# HCRT_STM32_Sch.net
KiCad netlist of a schematic drawn in Altium Designer
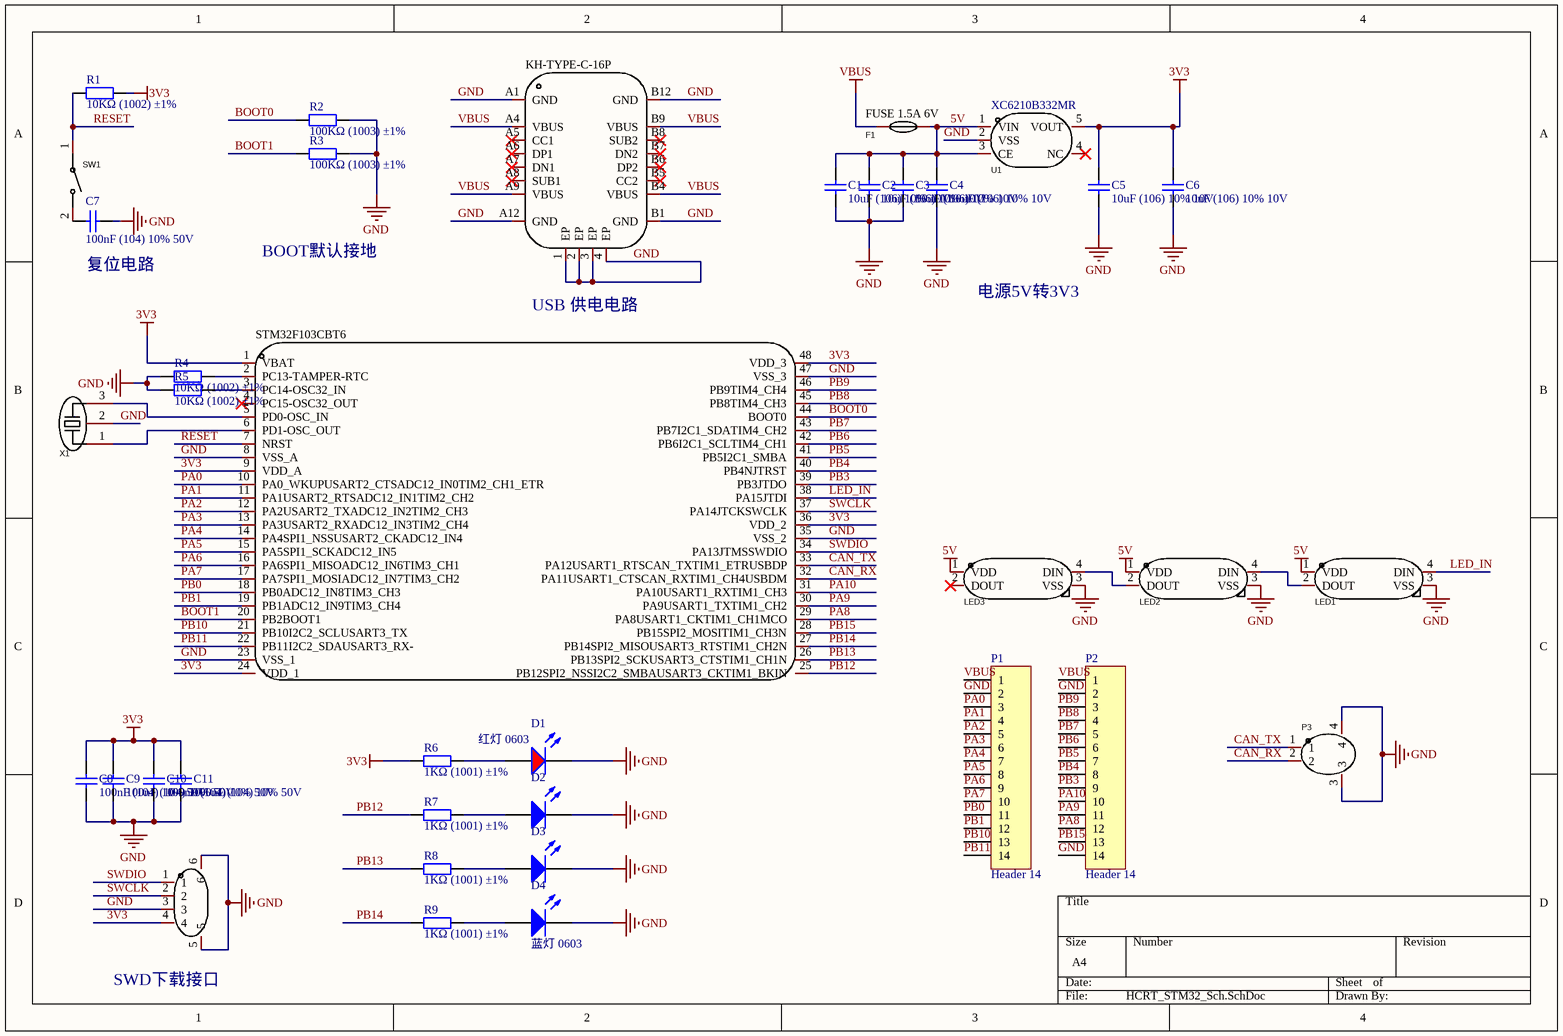
[diagram p0: HCRT_STM32_Sch.SchDoc]

(export (version "E")
  (design (tool "Eeschema 10.0.6"))
  (components
    (comp (ref "C1")
      (value "10uF (106) 10% 10V")
      (footprint "0603_C")
      (description "贴片电容")
      (libsource (lib "Miscellaneous Devices LC") (part "0603 10uF (106) 10% 10V"))
    )
    (comp (ref "C2")
      (value "10uF (106) 10% 10V")
      (footprint "0603_C")
      (description "贴片电容")
      (libsource (lib "Miscellaneous Devices LC") (part "0603 10uF (106) 10% 10V"))
    )
    (comp (ref "C3")
      (value "10uF (106) 10% 10V")
      (footprint "0603_C")
      (description "贴片电容")
      (libsource (lib "Miscellaneous Devices LC") (part "0603 10uF (106) 10% 10V"))
    )
    (comp (ref "C4")
      (value "10uF (106) 10% 10V")
      (footprint "0603_C")
      (description "贴片电容")
      (libsource (lib "Miscellaneous Devices LC") (part "0603 10uF (106) 10% 10V"))
    )
    (comp (ref "C5")
      (value "10uF (106) 10% 10V")
      (footprint "0603_C")
      (description "贴片电容")
      (libsource (lib "Miscellaneous Devices LC") (part "0603 10uF (106) 10% 10V"))
    )
    (comp (ref "C6")
      (value "10uF (106) 10% 10V")
      (footprint "0603_C")
      (description "贴片电容")
      (libsource (lib "Miscellaneous Devices LC") (part "0603 10uF (106) 10% 10V"))
    )
    (comp (ref "C7")
      (value "100nF (104) 10% 50V")
      (footprint "0603_C")
      (description "贴片电容")
      (libsource (lib "Miscellaneous Devices LC") (part "0603 100nF (104) 10% 50V"))
    )
    (comp (ref "C8")
      (value "100nF (104) 10% 50V")
      (footprint "0603_C")
      (description "贴片电容")
      (libsource (lib "Miscellaneous Devices LC") (part "0603 100nF (104) 10% 50V"))
    )
    (comp (ref "C9")
      (value "100nF (104) 10% 50V")
      (footprint "0603_C")
      (description "贴片电容")
      (libsource (lib "Miscellaneous Devices LC") (part "0603 100nF (104) 10% 50V"))
    )
    (comp (ref "C10")
      (value "100nF (104) 10% 50V")
      (footprint "0603_C")
      (description "贴片电容")
      (libsource (lib "Miscellaneous Devices LC") (part "0603 100nF (104) 10% 50V"))
    )
    (comp (ref "C11")
      (value "100nF (104) 10% 50V")
      (footprint "0603_C")
      (description "贴片电容")
      (libsource (lib "Miscellaneous Devices LC") (part "0603 100nF (104) 10% 50V"))
    )
    (comp (ref "CN1")
      (value "HC-1.25-4PWT")
      (footprint "CONN-SMD_4P-P1.25-HC-1.25-4PWT")
      (fields (field (name "MANUFACTURER") "HCTL(华灿天禄)"))
      (libsource (lib "zxy's_LIB") (part "HC-1.25-4PWT"))
    )
    (comp (ref "D1")
      (value "红灯 0603")
      (footprint "0603_LED_S1")
      (description "发光二极管")
      (libsource (lib "Miscellaneous Devices LC") (part "0603 红灯"))
    )
    (comp (ref "D2")
      (value "蓝灯 0603")
      (footprint "0603_LED_S1")
      (description "发光二极管")
      (libsource (lib "Miscellaneous Devices LC") (part "0603 蓝灯"))
    )
    (comp (ref "D3")
      (value "蓝灯 0603")
      (footprint "0603_LED_S1")
      (description "发光二极管")
      (libsource (lib "Miscellaneous Devices LC") (part "0603 蓝灯"))
    )
    (comp (ref "D4")
      (value "蓝灯 0603")
      (footprint "0603_LED_S1")
      (description "发光二极管")
      (libsource (lib "Miscellaneous Devices LC") (part "0603 蓝灯"))
    )
    (comp (ref "F1")
      (value "FUSE0603")
      (footprint "F0603")
      (fields (field (name "MANUFACTURER") "BHFUSE(佰宏)") (field (name "MANUFACTURER PART") "BSMD0603L-150"))
      (libsource (lib "zxy's_LIB") (part "FUSE0603"))
    )
    (comp (ref "LED1")
      (value "WS2812C")
      (footprint "LED-SMD_4P-L5.0-W5.0-LS5.4-TL-1")
      (fields (field (name "MANUFACTURER") "worldsemi"))
      (libsource (lib "zxy's_LIB") (part "WS2812C"))
    )
    (comp (ref "LED2")
      (value "WS2812C")
      (footprint "LED-SMD_4P-L5.0-W5.0-LS5.4-TL-1")
      (fields (field (name "MANUFACTURER") "worldsemi"))
      (libsource (lib "zxy's_LIB") (part "WS2812C"))
    )
    (comp (ref "LED3")
      (value "WS2812C")
      (footprint "LED-SMD_4P-L5.0-W5.0-LS5.4-TL-1")
      (fields (field (name "MANUFACTURER") "worldsemi"))
      (libsource (lib "zxy's_LIB") (part "WS2812C"))
    )
    (comp (ref "P1")
      (value "Header 14")
      (footprint "HDR1X14")
      (description "Header, 14-Pin")
      (fields (field (name "PUBLISHER") "Altium Limited"))
      (libsource (lib "Miscellaneous Connectors") (part "Header 14"))
    )
    (comp (ref "P2")
      (value "Header 14")
      (footprint "HDR1X14")
      (description "Header, 14-Pin")
      (fields (field (name "PUBLISHER") "Altium Limited"))
      (libsource (lib "Miscellaneous Connectors") (part "Header 14"))
    )
    (comp (ref "P3")
      (value "1.25_2P")
      (footprint "CONN-SMD_SM02B-GHS-TB-LF-SN")
      (fields (field (name "MANUFACTURER") "JST") (field (name "MANUFACTURER PART") "SM02B-GHS-TB(LF)(SN)"))
      (libsource (lib "zxy's_LIB") (part "1.25_2P"))
    )
    (comp (ref "R1")
      (value "10KΩ (1002) ±1%")
      (footprint "0603_R")
      (description "贴片电阻")
      (libsource (lib "Miscellaneous Devices LC") (part "0603 10KΩ (1002) 1%"))
    )
    (comp (ref "R2")
      (value "100KΩ (1003) ±1%")
      (footprint "0603_R")
      (description "贴片电阻")
      (libsource (lib "Miscellaneous Devices LC") (part "0603 100KΩ (1003) 1%"))
    )
    (comp (ref "R3")
      (value "100KΩ (1003) ±1%")
      (footprint "0603_R")
      (description "贴片电阻")
      (libsource (lib "Miscellaneous Devices LC") (part "0603 100KΩ (1003) 1%"))
    )
    (comp (ref "R4")
      (value "10KΩ (1002) ±1%")
      (footprint "0603_R")
      (description "贴片电阻")
      (libsource (lib "Miscellaneous Devices LC") (part "0603 10KΩ (1002) 1%"))
    )
    (comp (ref "R5")
      (value "10KΩ (1002) ±1%")
      (footprint "0603_R")
      (description "贴片电阻")
      (libsource (lib "Miscellaneous Devices LC") (part "0603 10KΩ (1002) 1%"))
    )
    (comp (ref "R6")
      (value "1KΩ (1001) ±1%")
      (footprint "0603_R")
      (description "贴片电阻")
      (libsource (lib "Miscellaneous Devices LC") (part "0603 1KΩ (1001) 1%"))
    )
    (comp (ref "R7")
      (value "1KΩ (1001) ±1%")
      (footprint "0603_R")
      (description "贴片电阻")
      (libsource (lib "Miscellaneous Devices LC") (part "0603 1KΩ (1001) 1%"))
    )
    (comp (ref "R8")
      (value "1KΩ (1001) ±1%")
      (footprint "0603_R")
      (description "贴片电阻")
      (libsource (lib "Miscellaneous Devices LC") (part "0603 1KΩ (1001) 1%"))
    )
    (comp (ref "R9")
      (value "1KΩ (1001) ±1%")
      (footprint "0603_R")
      (description "贴片电阻")
      (libsource (lib "Miscellaneous Devices LC") (part "0603 1KΩ (1001) 1%"))
    )
    (comp (ref "SW1")
      (value "K2-1107ST-A4DW-06_C118141")
      (footprint "KEY-SMD_L6.2-W3.6-LS8.0")
      (fields (field (name "MANUFACTURER") "韩国韩荣") (field (name "MANUFACTURER PART") "K2-1107ST-A4DW-06"))
      (libsource (lib "zxy's_LIB") (part "K2-1107ST-A4DW-06_C118141"))
    )
    (comp (ref "U1")
      (value "XC6210B332MR")
      (footprint "SOT-23-5_L3.0-W1.7-P0.95-LS2.8-BR")
      (fields (field (name "MANUFACTURER") "TOREX(特瑞仕)"))
      (libsource (lib "zxy's_LIB") (part "XC6210B332MR"))
    )
    (comp (ref "U2")
      (value "STM32F103CBT6")
      (footprint "LQFP-48_L7.0-W7.0-P0.50-LS9.0-BL")
      (fields (field (name "MANUFACTURER") "ST(意法半导体)"))
      (libsource (lib "zxy's_LIB") (part "STM32F103CBT6"))
    )
    (comp (ref "USB1")
      (value "KH-TYPE-C-16P")
      (footprint "USB-C-SMD_KH-TYPE-C-16P")
      (fields (field (name "MANUFACTURER") "kinghelm(金航标)"))
      (libsource (lib "zxy's_LIB") (part "KH-TYPE-C-16P"))
    )
    (comp (ref "X1")
      (value "CSTCE8M00G15C99-R0")
      (footprint "OSC-SMD_3P-L3.2-W1.3-P1.2-L")
      (fields (field (name "MANUFACTURER") "muRata(村田)"))
      (libsource (lib "zxy's_LIB") (part "CSTCE8M00G15C99-R0"))
    )
  )
  (nets
    (net (code "1") (name "/BOOT0") (class "Default")
      (node (ref "R2") (pin "1") (pinfunction "1_1") (pintype "passive"))
      (node (ref "U2") (pin "44") (pinfunction "BOOT0_44") (pintype "passive"))
    )
    (net (code "2") (name "/BOOT1") (class "Default")
      (node (ref "R3") (pin "1") (pinfunction "1_1") (pintype "passive"))
      (node (ref "U2") (pin "20") (pinfunction "PB2BOOT1_20") (pintype "passive"))
    )
    (net (code "3") (name "/CAN_RX") (class "Default")
      (node (ref "P3") (pin "2") (pinfunction "2_2") (pintype "passive"))
      (node (ref "U2") (pin "32") (pinfunction "PA11USART1_CTSCAN_RXTIM1_CH4USBDM_32") (pintype "passive"))
    )
    (net (code "4") (name "/CAN_TX") (class "Default")
      (node (ref "P3") (pin "1") (pinfunction "1_1") (pintype "passive"))
      (node (ref "U2") (pin "33") (pinfunction "PA12USART1_RTSCAN_TXTIM1_ETRUSBDP_33") (pintype "passive"))
    )
    (net (code "5") (name "/LED_IN") (class "Default")
      (node (ref "LED1") (pin "4") (pinfunction "DIN_4") (pintype "passive"))
      (node (ref "U2") (pin "38") (pinfunction "PA15JTDI_38") (pintype "passive"))
    )
    (net (code "6") (name "/PA0") (class "Default")
      (node (ref "P1") (pin "3") (pinfunction "3_3") (pintype "passive"))
      (node (ref "U2") (pin "10") (pinfunction "PA0_WKUPUSART2_CTSADC12_IN0TIM2_CH1_ETR_10") (pintype "passive"))
    )
    (net (code "7") (name "/PA1") (class "Default")
      (node (ref "P1") (pin "4") (pinfunction "4_4") (pintype "passive"))
      (node (ref "U2") (pin "11") (pinfunction "PA1USART2_RTSADC12_IN1TIM2_CH2_11") (pintype "passive"))
    )
    (net (code "8") (name "/PA2") (class "Default")
      (node (ref "P1") (pin "5") (pinfunction "5_5") (pintype "passive"))
      (node (ref "U2") (pin "12") (pinfunction "PA2USART2_TXADC12_IN2TIM2_CH3_12") (pintype "passive"))
    )
    (net (code "9") (name "/PA3") (class "Default")
      (node (ref "P1") (pin "6") (pinfunction "6_6") (pintype "passive"))
      (node (ref "U2") (pin "13") (pinfunction "PA3USART2_RXADC12_IN3TIM2_CH4_13") (pintype "passive"))
    )
    (net (code "10") (name "/PA4") (class "Default")
      (node (ref "P1") (pin "7") (pinfunction "7_7") (pintype "passive"))
      (node (ref "U2") (pin "14") (pinfunction "PA4SPI1_NSSUSART2_CKADC12_IN4_14") (pintype "passive"))
    )
    (net (code "11") (name "/PA5") (class "Default")
      (node (ref "P1") (pin "8") (pinfunction "8_8") (pintype "passive"))
      (node (ref "U2") (pin "15") (pinfunction "PA5SPI1_SCKADC12_IN5_15") (pintype "passive"))
    )
    (net (code "12") (name "/PA6") (class "Default")
      (node (ref "P1") (pin "9") (pinfunction "9_9") (pintype "passive"))
      (node (ref "U2") (pin "16") (pinfunction "PA6SPI1_MISOADC12_IN6TIM3_CH1_16") (pintype "passive"))
    )
    (net (code "13") (name "/PA7") (class "Default")
      (node (ref "P1") (pin "10") (pinfunction "10_10") (pintype "passive"))
      (node (ref "U2") (pin "17") (pinfunction "PA7SPI1_MOSIADC12_IN7TIM3_CH2_17") (pintype "passive"))
    )
    (net (code "14") (name "/PA8") (class "Default")
      (node (ref "P2") (pin "12") (pinfunction "12_12") (pintype "passive"))
      (node (ref "U2") (pin "29") (pinfunction "PA8USART1_CKTIM1_CH1MCO_29") (pintype "passive"))
    )
    (net (code "15") (name "/PA9") (class "Default")
      (node (ref "P2") (pin "11") (pinfunction "11_11") (pintype "passive"))
      (node (ref "U2") (pin "30") (pinfunction "PA9USART1_TXTIM1_CH2_30") (pintype "passive"))
    )
    (net (code "16") (name "/PA10") (class "Default")
      (node (ref "P2") (pin "10") (pinfunction "10_10") (pintype "passive"))
      (node (ref "U2") (pin "31") (pinfunction "PA10USART1_RXTIM1_CH3_31") (pintype "passive"))
    )
    (net (code "17") (name "/PB0") (class "Default")
      (node (ref "P1") (pin "11") (pinfunction "11_11") (pintype "passive"))
      (node (ref "U2") (pin "18") (pinfunction "PB0ADC12_IN8TIM3_CH3_18") (pintype "passive"))
    )
    (net (code "18") (name "/PB1") (class "Default")
      (node (ref "P1") (pin "12") (pinfunction "12_12") (pintype "passive"))
      (node (ref "U2") (pin "19") (pinfunction "PB1ADC12_IN9TIM3_CH4_19") (pintype "passive"))
    )
    (net (code "19") (name "/PB3") (class "Default")
      (node (ref "P2") (pin "9") (pinfunction "9_9") (pintype "passive"))
      (node (ref "U2") (pin "39") (pinfunction "PB3JTDO_39") (pintype "passive"))
    )
    (net (code "20") (name "/PB4") (class "Default")
      (node (ref "P2") (pin "8") (pinfunction "8_8") (pintype "passive"))
      (node (ref "U2") (pin "40") (pinfunction "PB4NJTRST_40") (pintype "passive"))
    )
    (net (code "21") (name "/PB5") (class "Default")
      (node (ref "P2") (pin "7") (pinfunction "7_7") (pintype "passive"))
      (node (ref "U2") (pin "41") (pinfunction "PB5I2C1_SMBA_41") (pintype "passive"))
    )
    (net (code "22") (name "/PB6") (class "Default")
      (node (ref "P2") (pin "6") (pinfunction "6_6") (pintype "passive"))
      (node (ref "U2") (pin "42") (pinfunction "PB6I2C1_SCLTIM4_CH1_42") (pintype "passive"))
    )
    (net (code "23") (name "/PB7") (class "Default")
      (node (ref "P2") (pin "5") (pinfunction "5_5") (pintype "passive"))
      (node (ref "U2") (pin "43") (pinfunction "PB7I2C1_SDATIM4_CH2_43") (pintype "passive"))
    )
    (net (code "24") (name "/PB8") (class "Default")
      (node (ref "P2") (pin "4") (pinfunction "4_4") (pintype "passive"))
      (node (ref "U2") (pin "45") (pinfunction "PB8TIM4_CH3_45") (pintype "passive"))
    )
    (net (code "25") (name "/PB9") (class "Default")
      (node (ref "P2") (pin "3") (pinfunction "3_3") (pintype "passive"))
      (node (ref "U2") (pin "46") (pinfunction "PB9TIM4_CH4_46") (pintype "passive"))
    )
    (net (code "26") (name "/PB10") (class "Default")
      (node (ref "P1") (pin "13") (pinfunction "13_13") (pintype "passive"))
      (node (ref "U2") (pin "21") (pinfunction "PB10I2C2_SCLUSART3_TX_21") (pintype "passive"))
    )
    (net (code "27") (name "/PB11") (class "Default")
      (node (ref "P1") (pin "14") (pinfunction "14_14") (pintype "passive"))
      (node (ref "U2") (pin "22") (pinfunction "PB11I2C2_SDAUSART3_RX-_22") (pintype "passive"))
    )
    (net (code "28") (name "/PB12") (class "Default")
      (node (ref "R7") (pin "1") (pinfunction "1_1") (pintype "passive"))
      (node (ref "U2") (pin "25") (pinfunction "PB12SPI2_NSSI2C2_SMBAUSART3_CKTIM1_BKIN_25") (pintype "passive"))
    )
    (net (code "29") (name "/PB13") (class "Default")
      (node (ref "R8") (pin "1") (pinfunction "1_1") (pintype "passive"))
      (node (ref "U2") (pin "26") (pinfunction "PB13SPI2_SCKUSART3_CTSTIM1_CH1N_26") (pintype "passive"))
    )
    (net (code "30") (name "/PB14") (class "Default")
      (node (ref "R9") (pin "1") (pinfunction "1_1") (pintype "passive"))
      (node (ref "U2") (pin "27") (pinfunction "PB14SPI2_MISOUSART3_RTSTIM1_CH2N_27") (pintype "passive"))
    )
    (net (code "31") (name "/PB15") (class "Default")
      (node (ref "P2") (pin "13") (pinfunction "13_13") (pintype "passive"))
      (node (ref "U2") (pin "28") (pinfunction "PB15SPI2_MOSITIM1_CH3N_28") (pintype "passive"))
    )
    (net (code "32") (name "/RESET") (class "Default")
      (node (ref "R1") (pin "1") (pinfunction "1_1") (pintype "passive"))
      (node (ref "SW1") (pin "1") (pinfunction "1_1") (pintype "passive"))
      (node (ref "U2") (pin "7") (pinfunction "NRST_7") (pintype "passive"))
    )
    (net (code "33") (name "/SWCLK") (class "Default")
      (node (ref "CN1") (pin "2") (pinfunction "2_2") (pintype "passive"))
      (node (ref "U2") (pin "37") (pinfunction "PA14JTCKSWCLK_37") (pintype "passive"))
    )
    (net (code "34") (name "/SWDIO") (class "Default")
      (node (ref "CN1") (pin "1") (pinfunction "1_1") (pintype "passive"))
      (node (ref "U2") (pin "34") (pinfunction "PA13JTMSSWDIO_34") (pintype "passive"))
    )
    (net (code "35") (name "3V3") (class "Default")
      (node (ref "C10") (pin "2") (pinfunction "2_2") (pintype "passive"))
      (node (ref "C11") (pin "2") (pinfunction "2_2") (pintype "passive"))
      (node (ref "C5") (pin "2") (pinfunction "2_2") (pintype "passive"))
      (node (ref "C6") (pin "2") (pinfunction "2_2") (pintype "passive"))
      (node (ref "C8") (pin "2") (pinfunction "2_2") (pintype "passive"))
      (node (ref "C9") (pin "2") (pinfunction "2_2") (pintype "passive"))
      (node (ref "CN1") (pin "4") (pinfunction "4_4") (pintype "passive"))
      (node (ref "R1") (pin "2") (pinfunction "2_2") (pintype "passive"))
      (node (ref "R6") (pin "1") (pinfunction "1_1") (pintype "passive"))
      (node (ref "U1") (pin "5") (pinfunction "VOUT_5") (pintype "passive"))
      (node (ref "U2") (pin "1") (pinfunction "VBAT_1") (pintype "passive"))
      (node (ref "U2") (pin "24") (pinfunction "VDD_1_24") (pintype "passive"))
      (node (ref "U2") (pin "36") (pinfunction "VDD_2_36") (pintype "passive"))
      (node (ref "U2") (pin "48") (pinfunction "VDD_3_48") (pintype "passive"))
      (node (ref "U2") (pin "9") (pinfunction "VDD_A_9") (pintype "passive"))
    )
    (net (code "36") (name "5V") (class "Default")
      (node (ref "C1") (pin "2") (pinfunction "2_2") (pintype "passive"))
      (node (ref "C2") (pin "2") (pinfunction "2_2") (pintype "passive"))
      (node (ref "C3") (pin "2") (pinfunction "2_2") (pintype "passive"))
      (node (ref "C4") (pin "2") (pinfunction "2_2") (pintype "passive"))
      (node (ref "F1") (pin "2") (pinfunction "2_2") (pintype "passive"))
      (node (ref "LED1") (pin "1") (pinfunction "VDD_1") (pintype "passive"))
      (node (ref "LED2") (pin "1") (pinfunction "VDD_1") (pintype "passive"))
      (node (ref "LED3") (pin "1") (pinfunction "VDD_1") (pintype "passive"))
      (node (ref "U1") (pin "1") (pinfunction "VIN_1") (pintype "passive"))
      (node (ref "U1") (pin "3") (pinfunction "CE_3") (pintype "passive"))
    )
    (net (code "37") (name "GND") (class "Default")
      (node (ref "C1") (pin "1") (pinfunction "1_1") (pintype "passive"))
      (node (ref "C10") (pin "1") (pinfunction "1_1") (pintype "passive"))
      (node (ref "C11") (pin "1") (pinfunction "1_1") (pintype "passive"))
      (node (ref "C2") (pin "1") (pinfunction "1_1") (pintype "passive"))
      (node (ref "C3") (pin "1") (pinfunction "1_1") (pintype "passive"))
      (node (ref "C4") (pin "1") (pinfunction "1_1") (pintype "passive"))
      (node (ref "C5") (pin "1") (pinfunction "1_1") (pintype "passive"))
      (node (ref "C6") (pin "1") (pinfunction "1_1") (pintype "passive"))
      (node (ref "C7") (pin "2") (pinfunction "2_2") (pintype "passive"))
      (node (ref "C8") (pin "1") (pinfunction "1_1") (pintype "passive"))
      (node (ref "C9") (pin "1") (pinfunction "1_1") (pintype "passive"))
      (node (ref "CN1") (pin "3") (pinfunction "3_3") (pintype "passive"))
      (node (ref "CN1") (pin "5") (pinfunction "5_5") (pintype "passive"))
      (node (ref "CN1") (pin "6") (pinfunction "6_6") (pintype "passive"))
      (node (ref "D1") (pin "K") (pinfunction "K_K") (pintype "passive"))
      (node (ref "D2") (pin "K") (pinfunction "K_K") (pintype "passive"))
      (node (ref "D3") (pin "K") (pinfunction "K_K") (pintype "passive"))
      (node (ref "D4") (pin "K") (pinfunction "K_K") (pintype "passive"))
      (node (ref "LED1") (pin "3") (pinfunction "VSS_3") (pintype "passive"))
      (node (ref "LED2") (pin "3") (pinfunction "VSS_3") (pintype "passive"))
      (node (ref "LED3") (pin "3") (pinfunction "VSS_3") (pintype "passive"))
      (node (ref "P1") (pin "2") (pinfunction "2_2") (pintype "passive"))
      (node (ref "P2") (pin "14") (pinfunction "14_14") (pintype "passive"))
      (node (ref "P2") (pin "2") (pinfunction "2_2") (pintype "passive"))
      (node (ref "P3") (pin "3") (pinfunction "3_3") (pintype "passive"))
      (node (ref "P3") (pin "4") (pinfunction "4_4") (pintype "passive"))
      (node (ref "R2") (pin "2") (pinfunction "2_2") (pintype "passive"))
      (node (ref "R3") (pin "2") (pinfunction "2_2") (pintype "passive"))
      (node (ref "R4") (pin "1") (pinfunction "1_1") (pintype "passive"))
      (node (ref "R5") (pin "1") (pinfunction "1_1") (pintype "passive"))
      (node (ref "U1") (pin "2") (pinfunction "VSS_2") (pintype "passive"))
      (node (ref "U2") (pin "23") (pinfunction "VSS_1_23") (pintype "passive"))
      (node (ref "U2") (pin "35") (pinfunction "VSS_2_35") (pintype "passive"))
      (node (ref "U2") (pin "47") (pinfunction "VSS_3_47") (pintype "passive"))
      (node (ref "U2") (pin "8") (pinfunction "VSS_A_8") (pintype "passive"))
      (node (ref "USB1") (pin "1") (pinfunction "EP_1") (pintype "passive"))
      (node (ref "USB1") (pin "2") (pinfunction "EP_2") (pintype "passive"))
      (node (ref "USB1") (pin "3") (pinfunction "EP_3") (pintype "passive"))
      (node (ref "USB1") (pin "4") (pinfunction "EP_4") (pintype "passive"))
      (node (ref "USB1") (pin "A1") (pinfunction "GND_A1") (pintype "passive"))
      (node (ref "USB1") (pin "A12") (pinfunction "GND_A12") (pintype "passive"))
      (node (ref "USB1") (pin "B1") (pinfunction "GND_B1") (pintype "passive"))
      (node (ref "USB1") (pin "B12") (pinfunction "GND_B12") (pintype "passive"))
      (node (ref "X1") (pin "2") (pinfunction "2_2") (pintype "passive"))
    )
    (net (code "38") (name "Net-(C7-Pad1)") (class "Default")
      (node (ref "C7") (pin "1") (pinfunction "1_1") (pintype "passive"))
      (node (ref "SW1") (pin "2") (pinfunction "2_2") (pintype "passive"))
    )
    (net (code "39") (name "Net-(D1-PadA)") (class "Default")
      (node (ref "D1") (pin "A") (pinfunction "A_A") (pintype "passive"))
      (node (ref "R6") (pin "2") (pinfunction "2_2") (pintype "passive"))
    )
    (net (code "40") (name "Net-(D2-PadA)") (class "Default")
      (node (ref "D2") (pin "A") (pinfunction "A_A") (pintype "passive"))
      (node (ref "R7") (pin "2") (pinfunction "2_2") (pintype "passive"))
    )
    (net (code "41") (name "Net-(D3-PadA)") (class "Default")
      (node (ref "D3") (pin "A") (pinfunction "A_A") (pintype "passive"))
      (node (ref "R8") (pin "2") (pinfunction "2_2") (pintype "passive"))
    )
    (net (code "42") (name "Net-(D4-PadA)") (class "Default")
      (node (ref "D4") (pin "A") (pinfunction "A_A") (pintype "passive"))
      (node (ref "R9") (pin "2") (pinfunction "2_2") (pintype "passive"))
    )
    (net (code "43") (name "Net-(LED1-DOUT)") (class "Default")
      (node (ref "LED1") (pin "2") (pinfunction "DOUT_2") (pintype "passive"))
      (node (ref "LED2") (pin "4") (pinfunction "DIN_4") (pintype "passive"))
    )
    (net (code "44") (name "Net-(LED2-DOUT)") (class "Default")
      (node (ref "LED2") (pin "2") (pinfunction "DOUT_2") (pintype "passive"))
      (node (ref "LED3") (pin "4") (pinfunction "DIN_4") (pintype "passive"))
    )
    (net (code "45") (name "Net-(U2-PC13-TAMPER-RTC)") (class "Default")
      (node (ref "R4") (pin "2") (pinfunction "2_2") (pintype "passive"))
      (node (ref "U2") (pin "2") (pinfunction "PC13-TAMPER-RTC_2") (pintype "passive"))
    )
    (net (code "46") (name "Net-(U2-PC14-OSC32_IN)") (class "Default")
      (node (ref "R5") (pin "2") (pinfunction "2_2") (pintype "passive"))
      (node (ref "U2") (pin "3") (pinfunction "PC14-OSC32_IN_3") (pintype "passive"))
    )
    (net (code "47") (name "Net-(U2-PD0-OSC_IN)") (class "Default")
      (node (ref "U2") (pin "5") (pinfunction "PD0-OSC_IN_5") (pintype "passive"))
      (node (ref "X1") (pin "3") (pinfunction "3_3") (pintype "passive"))
    )
    (net (code "48") (name "Net-(U2-PD1-OSC_OUT)") (class "Default")
      (node (ref "U2") (pin "6") (pinfunction "PD1-OSC_OUT_6") (pintype "passive"))
      (node (ref "X1") (pin "1") (pinfunction "1_1") (pintype "passive"))
    )
    (net (code "49") (name "VBUS") (class "Default")
      (node (ref "F1") (pin "1") (pinfunction "1_1") (pintype "passive"))
      (node (ref "P1") (pin "1") (pinfunction "1_1") (pintype "passive"))
      (node (ref "P2") (pin "1") (pinfunction "1_1") (pintype "passive"))
      (node (ref "USB1") (pin "A4") (pinfunction "VBUS_A4") (pintype "passive"))
      (node (ref "USB1") (pin "A9") (pinfunction "VBUS_A9") (pintype "passive"))
      (node (ref "USB1") (pin "B4") (pinfunction "VBUS_B4") (pintype "passive"))
      (node (ref "USB1") (pin "B9") (pinfunction "VBUS_B9") (pintype "passive"))
    )
    (net (code "50") (name "unconnected-(LED3-DOUT-Pad2)") (class "Default")
      (node (ref "LED3") (pin "2") (pinfunction "DOUT_2") (pintype "passive+no_connect"))
    )
    (net (code "51") (name "unconnected-(U1-NC-Pad4)") (class "Default")
      (node (ref "U1") (pin "4") (pinfunction "NC_4") (pintype "passive+no_connect"))
    )
    (net (code "52") (name "unconnected-(U2-PC15-OSC32_OUT-Pad4)") (class "Default")
      (node (ref "U2") (pin "4") (pinfunction "PC15-OSC32_OUT_4") (pintype "passive+no_connect"))
    )
    (net (code "53") (name "unconnected-(USB1-CC1-PadA5)") (class "Default")
      (node (ref "USB1") (pin "A5") (pinfunction "CC1_A5") (pintype "passive+no_connect"))
    )
    (net (code "54") (name "unconnected-(USB1-CC2-PadB5)") (class "Default")
      (node (ref "USB1") (pin "B5") (pinfunction "CC2_B5") (pintype "passive+no_connect"))
    )
    (net (code "55") (name "unconnected-(USB1-DN1-PadA7)") (class "Default")
      (node (ref "USB1") (pin "A7") (pinfunction "DN1_A7") (pintype "passive+no_connect"))
    )
    (net (code "56") (name "unconnected-(USB1-DN2-PadB7)") (class "Default")
      (node (ref "USB1") (pin "B7") (pinfunction "DN2_B7") (pintype "passive+no_connect"))
    )
    (net (code "57") (name "unconnected-(USB1-DP1-PadA6)") (class "Default")
      (node (ref "USB1") (pin "A6") (pinfunction "DP1_A6") (pintype "passive+no_connect"))
    )
    (net (code "58") (name "unconnected-(USB1-DP2-PadB6)") (class "Default")
      (node (ref "USB1") (pin "B6") (pinfunction "DP2_B6") (pintype "passive+no_connect"))
    )
    (net (code "59") (name "unconnected-(USB1-SUB1-PadA8)") (class "Default")
      (node (ref "USB1") (pin "A8") (pinfunction "SUB1_A8") (pintype "passive+no_connect"))
    )
    (net (code "60") (name "unconnected-(USB1-SUB2-PadB8)") (class "Default")
      (node (ref "USB1") (pin "B8") (pinfunction "SUB2_B8") (pintype "passive+no_connect"))
    )
  )
)
